# IRLocalization.net
KiCad netlist of a schematic drawn in EAGLE
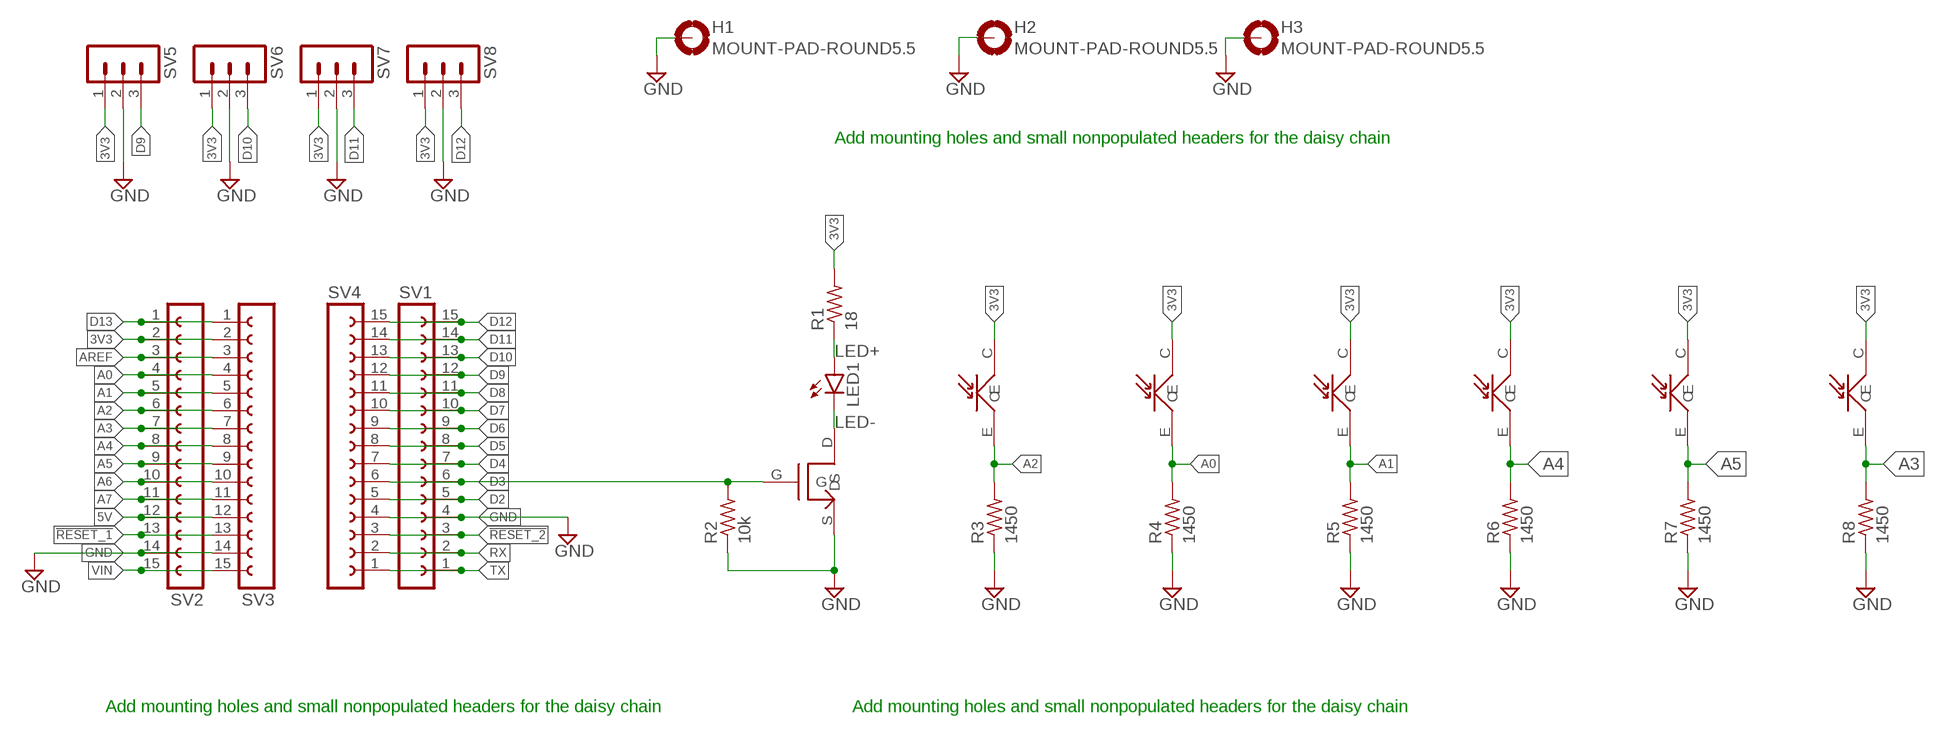
[diagram p0: schematic, sheet 1]

(export (version "E")
  (design (tool "Eeschema 10.0.6"))
  (components
    (comp (ref "H1")
      (value "MOUNT-PAD-ROUND5.5")
      (footprint "eagle-import:5,5-PAD")
      (libsource (lib "eagle-import") (part "MOUNT-PAD-ROUND5.5"))
    )
    (comp (ref "H2")
      (value "MOUNT-PAD-ROUND5.5")
      (footprint "eagle-import:5,5-PAD")
      (libsource (lib "eagle-import") (part "MOUNT-PAD-ROUND5.5"))
    )
    (comp (ref "H3")
      (value "MOUNT-PAD-ROUND5.5")
      (footprint "eagle-import:5,5-PAD")
      (libsource (lib "eagle-import") (part "MOUNT-PAD-ROUND5.5"))
    )
    (comp (ref "LED1")
      (value "LED5MM")
      (footprint "eagle-import:LED5MM")
      (libsource (lib "eagle-import") (part "LED5MM"))
    )
    (comp (ref "R1")
      (value "18")
      (footprint "eagle-import:R0603")
      (libsource (lib "eagle-import") (part "R-US_R0603"))
    )
    (comp (ref "R2")
      (value "10k")
      (footprint "eagle-import:R0603")
      (libsource (lib "eagle-import") (part "R-US_R0603"))
    )
    (comp (ref "R3")
      (value "1450")
      (footprint "eagle-import:R0603")
      (libsource (lib "eagle-import") (part "R-US_R0603"))
    )
    (comp (ref "R4")
      (value "1450")
      (footprint "eagle-import:R0603")
      (libsource (lib "eagle-import") (part "R-US_R0603"))
    )
    (comp (ref "R5")
      (value "1450")
      (footprint "eagle-import:R0603")
      (libsource (lib "eagle-import") (part "R-US_R0603"))
    )
    (comp (ref "R6")
      (value "1450")
      (footprint "eagle-import:R0603")
      (libsource (lib "eagle-import") (part "R-US_R0603"))
    )
    (comp (ref "R7")
      (value "1450")
      (footprint "eagle-import:R0603")
      (libsource (lib "eagle-import") (part "R-US_R0603"))
    )
    (comp (ref "R8")
      (value "1450")
      (footprint "eagle-import:R0603")
      (libsource (lib "eagle-import") (part "R-US_R0603"))
    )
    (comp (ref "SV1")
      (value "FE15-1")
      (footprint "eagle-import:FE15")
      (libsource (lib "eagle-import") (part "FE15-1"))
    )
    (comp (ref "SV2")
      (value "FE15-1")
      (footprint "eagle-import:FE15")
      (libsource (lib "eagle-import") (part "FE15-1"))
    )
    (comp (ref "SV3")
      (value "FE15-1")
      (footprint "eagle-import:FE15")
      (libsource (lib "eagle-import") (part "FE15-1"))
    )
    (comp (ref "SV4")
      (value "FE15-1")
      (footprint "eagle-import:FE15")
      (libsource (lib "eagle-import") (part "FE15-1"))
    )
    (comp (ref "SV5")
      (value "MA03-1")
      (footprint "eagle-import:MA03-1")
      (libsource (lib "eagle-import") (part "MA03-1"))
    )
    (comp (ref "SV6")
      (value "MA03-1")
      (footprint "eagle-import:MA03-1")
      (libsource (lib "eagle-import") (part "MA03-1"))
    )
    (comp (ref "SV7")
      (value "MA03-1")
      (footprint "eagle-import:MA03-1")
      (libsource (lib "eagle-import") (part "MA03-1"))
    )
    (comp (ref "SV8")
      (value "MA03-1")
      (footprint "eagle-import:MA03-1")
      (libsource (lib "eagle-import") (part "MA03-1"))
    )
    (comp (ref "U$1")
      (value "NMOS_SOT23")
      (footprint "eagle-import:SOT23")
      (libsource (lib "eagle-import") (part "NMOS_SOT23"))
    )
    (comp (ref "U$2")
      (value "PHOTOTRANSISTOR_2.54")
      (footprint "eagle-import:2.54_TH")
      (libsource (lib "eagle-import") (part "PHOTOTRANSISTOR_2.54"))
    )
    (comp (ref "U$3")
      (value "PHOTOTRANSISTOR_2.54")
      (footprint "eagle-import:2.54_TH")
      (libsource (lib "eagle-import") (part "PHOTOTRANSISTOR_2.54"))
    )
    (comp (ref "U$4")
      (value "PHOTOTRANSISTOR_2.54")
      (footprint "eagle-import:2.54_TH")
      (libsource (lib "eagle-import") (part "PHOTOTRANSISTOR_2.54"))
    )
    (comp (ref "U$5")
      (value "PHOTOTRANSISTOR_2.54")
      (footprint "eagle-import:2.54_TH")
      (libsource (lib "eagle-import") (part "PHOTOTRANSISTOR_2.54"))
    )
    (comp (ref "U$6")
      (value "PHOTOTRANSISTOR_2.54")
      (footprint "eagle-import:2.54_TH")
      (libsource (lib "eagle-import") (part "PHOTOTRANSISTOR_2.54"))
    )
    (comp (ref "U$7")
      (value "PHOTOTRANSISTOR_2.54")
      (footprint "eagle-import:2.54_TH")
      (libsource (lib "eagle-import") (part "PHOTOTRANSISTOR_2.54"))
    )
  )
  (nets
    (net (code "1") (name "/LED+") (class "Default")
      (node (ref "LED1") (pin "A") (pinfunction "A_A") (pintype "passive"))
      (node (ref "R1") (pin "1") (pinfunction "1_1") (pintype "passive"))
    )
    (net (code "2") (name "/LED-") (class "Default")
      (node (ref "LED1") (pin "K") (pinfunction "C_K") (pintype "passive"))
      (node (ref "U$1") (pin "D") (pinfunction "D_D") (pintype "bidirectional"))
    )
    (net (code "3") (name "/~{RESET_1}") (class "Default")
      (node (ref "SV2") (pin "13") (pinfunction "13_13") (pintype "passive"))
      (node (ref "SV3") (pin "13") (pinfunction "13_13") (pintype "passive"))
    )
    (net (code "4") (name "/~{RESET_2}") (class "Default")
      (node (ref "SV1") (pin "3") (pinfunction "3_3") (pintype "passive"))
      (node (ref "SV4") (pin "3") (pinfunction "3_3") (pintype "passive"))
    )
    (net (code "5") (name "3V3") (class "Default")
      (node (ref "R1") (pin "2") (pinfunction "2_2") (pintype "passive"))
      (node (ref "SV2") (pin "2") (pinfunction "2_2") (pintype "passive"))
      (node (ref "SV3") (pin "2") (pinfunction "2_2") (pintype "passive"))
      (node (ref "SV5") (pin "1") (pinfunction "1_1") (pintype "passive"))
      (node (ref "SV6") (pin "1") (pinfunction "1_1") (pintype "passive"))
      (node (ref "SV7") (pin "1") (pinfunction "1_1") (pintype "passive"))
      (node (ref "SV8") (pin "1") (pinfunction "1_1") (pintype "passive"))
      (node (ref "U$2") (pin "C") (pinfunction "C_C") (pintype "bidirectional"))
      (node (ref "U$3") (pin "C") (pinfunction "C_C") (pintype "bidirectional"))
      (node (ref "U$4") (pin "C") (pinfunction "C_C") (pintype "bidirectional"))
      (node (ref "U$5") (pin "C") (pinfunction "C_C") (pintype "bidirectional"))
      (node (ref "U$6") (pin "C") (pinfunction "C_C") (pintype "bidirectional"))
      (node (ref "U$7") (pin "C") (pinfunction "C_C") (pintype "bidirectional"))
    )
    (net (code "6") (name "5V") (class "Default")
      (node (ref "SV2") (pin "12") (pinfunction "12_12") (pintype "passive"))
      (node (ref "SV3") (pin "12") (pinfunction "12_12") (pintype "passive"))
    )
    (net (code "7") (name "A0") (class "Default")
      (node (ref "R4") (pin "2") (pinfunction "2_2") (pintype "passive"))
      (node (ref "SV2") (pin "4") (pinfunction "4_4") (pintype "passive"))
      (node (ref "SV3") (pin "4") (pinfunction "4_4") (pintype "passive"))
      (node (ref "U$3") (pin "E") (pinfunction "E_E") (pintype "bidirectional"))
    )
    (net (code "8") (name "A1") (class "Default")
      (node (ref "R5") (pin "2") (pinfunction "2_2") (pintype "passive"))
      (node (ref "SV2") (pin "5") (pinfunction "5_5") (pintype "passive"))
      (node (ref "SV3") (pin "5") (pinfunction "5_5") (pintype "passive"))
      (node (ref "U$4") (pin "E") (pinfunction "E_E") (pintype "bidirectional"))
    )
    (net (code "9") (name "A2") (class "Default")
      (node (ref "R3") (pin "2") (pinfunction "2_2") (pintype "passive"))
      (node (ref "SV2") (pin "6") (pinfunction "6_6") (pintype "passive"))
      (node (ref "SV3") (pin "6") (pinfunction "6_6") (pintype "passive"))
      (node (ref "U$2") (pin "E") (pinfunction "E_E") (pintype "bidirectional"))
    )
    (net (code "10") (name "A3") (class "Default")
      (node (ref "R8") (pin "2") (pinfunction "2_2") (pintype "passive"))
      (node (ref "SV2") (pin "7") (pinfunction "7_7") (pintype "passive"))
      (node (ref "SV3") (pin "7") (pinfunction "7_7") (pintype "passive"))
      (node (ref "U$7") (pin "E") (pinfunction "E_E") (pintype "bidirectional"))
    )
    (net (code "11") (name "A4") (class "Default")
      (node (ref "R6") (pin "2") (pinfunction "2_2") (pintype "passive"))
      (node (ref "SV2") (pin "8") (pinfunction "8_8") (pintype "passive"))
      (node (ref "SV3") (pin "8") (pinfunction "8_8") (pintype "passive"))
      (node (ref "U$5") (pin "E") (pinfunction "E_E") (pintype "bidirectional"))
    )
    (net (code "12") (name "A5") (class "Default")
      (node (ref "R7") (pin "2") (pinfunction "2_2") (pintype "passive"))
      (node (ref "SV2") (pin "9") (pinfunction "9_9") (pintype "passive"))
      (node (ref "SV3") (pin "9") (pinfunction "9_9") (pintype "passive"))
      (node (ref "U$6") (pin "E") (pinfunction "E_E") (pintype "bidirectional"))
    )
    (net (code "13") (name "A6") (class "Default")
      (node (ref "SV2") (pin "10") (pinfunction "10_10") (pintype "passive"))
      (node (ref "SV3") (pin "10") (pinfunction "10_10") (pintype "passive"))
    )
    (net (code "14") (name "A7") (class "Default")
      (node (ref "SV2") (pin "11") (pinfunction "11_11") (pintype "passive"))
      (node (ref "SV3") (pin "11") (pinfunction "11_11") (pintype "passive"))
    )
    (net (code "15") (name "AREF") (class "Default")
      (node (ref "SV2") (pin "3") (pinfunction "3_3") (pintype "passive"))
      (node (ref "SV3") (pin "3") (pinfunction "3_3") (pintype "passive"))
    )
    (net (code "16") (name "D2") (class "Default")
      (node (ref "SV1") (pin "5") (pinfunction "5_5") (pintype "passive"))
      (node (ref "SV4") (pin "5") (pinfunction "5_5") (pintype "passive"))
    )
    (net (code "17") (name "D3") (class "Default")
      (node (ref "R2") (pin "2") (pinfunction "2_2") (pintype "passive"))
      (node (ref "SV1") (pin "6") (pinfunction "6_6") (pintype "passive"))
      (node (ref "SV4") (pin "6") (pinfunction "6_6") (pintype "passive"))
      (node (ref "U$1") (pin "G") (pinfunction "G_G") (pintype "bidirectional"))
    )
    (net (code "18") (name "D4") (class "Default")
      (node (ref "SV1") (pin "7") (pinfunction "7_7") (pintype "passive"))
      (node (ref "SV4") (pin "7") (pinfunction "7_7") (pintype "passive"))
    )
    (net (code "19") (name "D5") (class "Default")
      (node (ref "SV1") (pin "8") (pinfunction "8_8") (pintype "passive"))
      (node (ref "SV4") (pin "8") (pinfunction "8_8") (pintype "passive"))
    )
    (net (code "20") (name "D6") (class "Default")
      (node (ref "SV1") (pin "9") (pinfunction "9_9") (pintype "passive"))
      (node (ref "SV4") (pin "9") (pinfunction "9_9") (pintype "passive"))
    )
    (net (code "21") (name "D7") (class "Default")
      (node (ref "SV1") (pin "10") (pinfunction "10_10") (pintype "passive"))
      (node (ref "SV4") (pin "10") (pinfunction "10_10") (pintype "passive"))
    )
    (net (code "22") (name "D8") (class "Default")
      (node (ref "SV1") (pin "11") (pinfunction "11_11") (pintype "passive"))
      (node (ref "SV4") (pin "11") (pinfunction "11_11") (pintype "passive"))
    )
    (net (code "23") (name "D9") (class "Default")
      (node (ref "SV1") (pin "12") (pinfunction "12_12") (pintype "passive"))
      (node (ref "SV4") (pin "12") (pinfunction "12_12") (pintype "passive"))
      (node (ref "SV5") (pin "3") (pinfunction "3_3") (pintype "passive"))
    )
    (net (code "24") (name "D10") (class "Default")
      (node (ref "SV1") (pin "13") (pinfunction "13_13") (pintype "passive"))
      (node (ref "SV4") (pin "13") (pinfunction "13_13") (pintype "passive"))
      (node (ref "SV6") (pin "3") (pinfunction "3_3") (pintype "passive"))
    )
    (net (code "25") (name "D11") (class "Default")
      (node (ref "SV1") (pin "14") (pinfunction "14_14") (pintype "passive"))
      (node (ref "SV4") (pin "14") (pinfunction "14_14") (pintype "passive"))
      (node (ref "SV7") (pin "3") (pinfunction "3_3") (pintype "passive"))
    )
    (net (code "26") (name "D12") (class "Default")
      (node (ref "SV1") (pin "15") (pinfunction "15_15") (pintype "passive"))
      (node (ref "SV4") (pin "15") (pinfunction "15_15") (pintype "passive"))
      (node (ref "SV8") (pin "3") (pinfunction "3_3") (pintype "passive"))
    )
    (net (code "27") (name "D13") (class "Default")
      (node (ref "SV2") (pin "1") (pinfunction "1_1") (pintype "passive"))
      (node (ref "SV3") (pin "1") (pinfunction "1_1") (pintype "passive"))
    )
    (net (code "28") (name "GND") (class "Default")
      (node (ref "H1") (pin "B5,5") (pinfunction "MOUNT_B5,5") (pintype "passive"))
      (node (ref "H2") (pin "B5,5") (pinfunction "MOUNT_B5,5") (pintype "passive"))
      (node (ref "H3") (pin "B5,5") (pinfunction "MOUNT_B5,5") (pintype "passive"))
      (node (ref "R2") (pin "1") (pinfunction "1_1") (pintype "passive"))
      (node (ref "R3") (pin "1") (pinfunction "1_1") (pintype "passive"))
      (node (ref "R4") (pin "1") (pinfunction "1_1") (pintype "passive"))
      (node (ref "R5") (pin "1") (pinfunction "1_1") (pintype "passive"))
      (node (ref "R6") (pin "1") (pinfunction "1_1") (pintype "passive"))
      (node (ref "R7") (pin "1") (pinfunction "1_1") (pintype "passive"))
      (node (ref "R8") (pin "1") (pinfunction "1_1") (pintype "passive"))
      (node (ref "SV1") (pin "4") (pinfunction "4_4") (pintype "passive"))
      (node (ref "SV2") (pin "14") (pinfunction "14_14") (pintype "passive"))
      (node (ref "SV3") (pin "14") (pinfunction "14_14") (pintype "passive"))
      (node (ref "SV4") (pin "4") (pinfunction "4_4") (pintype "passive"))
      (node (ref "SV5") (pin "2") (pinfunction "2_2") (pintype "passive"))
      (node (ref "SV6") (pin "2") (pinfunction "2_2") (pintype "passive"))
      (node (ref "SV7") (pin "2") (pinfunction "2_2") (pintype "passive"))
      (node (ref "SV8") (pin "2") (pinfunction "2_2") (pintype "passive"))
      (node (ref "U$1") (pin "S") (pinfunction "S_S") (pintype "bidirectional"))
    )
    (net (code "29") (name "RX") (class "Default")
      (node (ref "SV1") (pin "2") (pinfunction "2_2") (pintype "passive"))
      (node (ref "SV4") (pin "2") (pinfunction "2_2") (pintype "passive"))
    )
    (net (code "30") (name "TX") (class "Default")
      (node (ref "SV1") (pin "1") (pinfunction "1_1") (pintype "passive"))
      (node (ref "SV4") (pin "1") (pinfunction "1_1") (pintype "passive"))
    )
    (net (code "31") (name "VIN") (class "Default")
      (node (ref "SV2") (pin "15") (pinfunction "15_15") (pintype "passive"))
      (node (ref "SV3") (pin "15") (pinfunction "15_15") (pintype "passive"))
    )
  )
)
